# OLED-Clock-6-nl.net
KiCad netlist of a schematic drawn in EAGLE
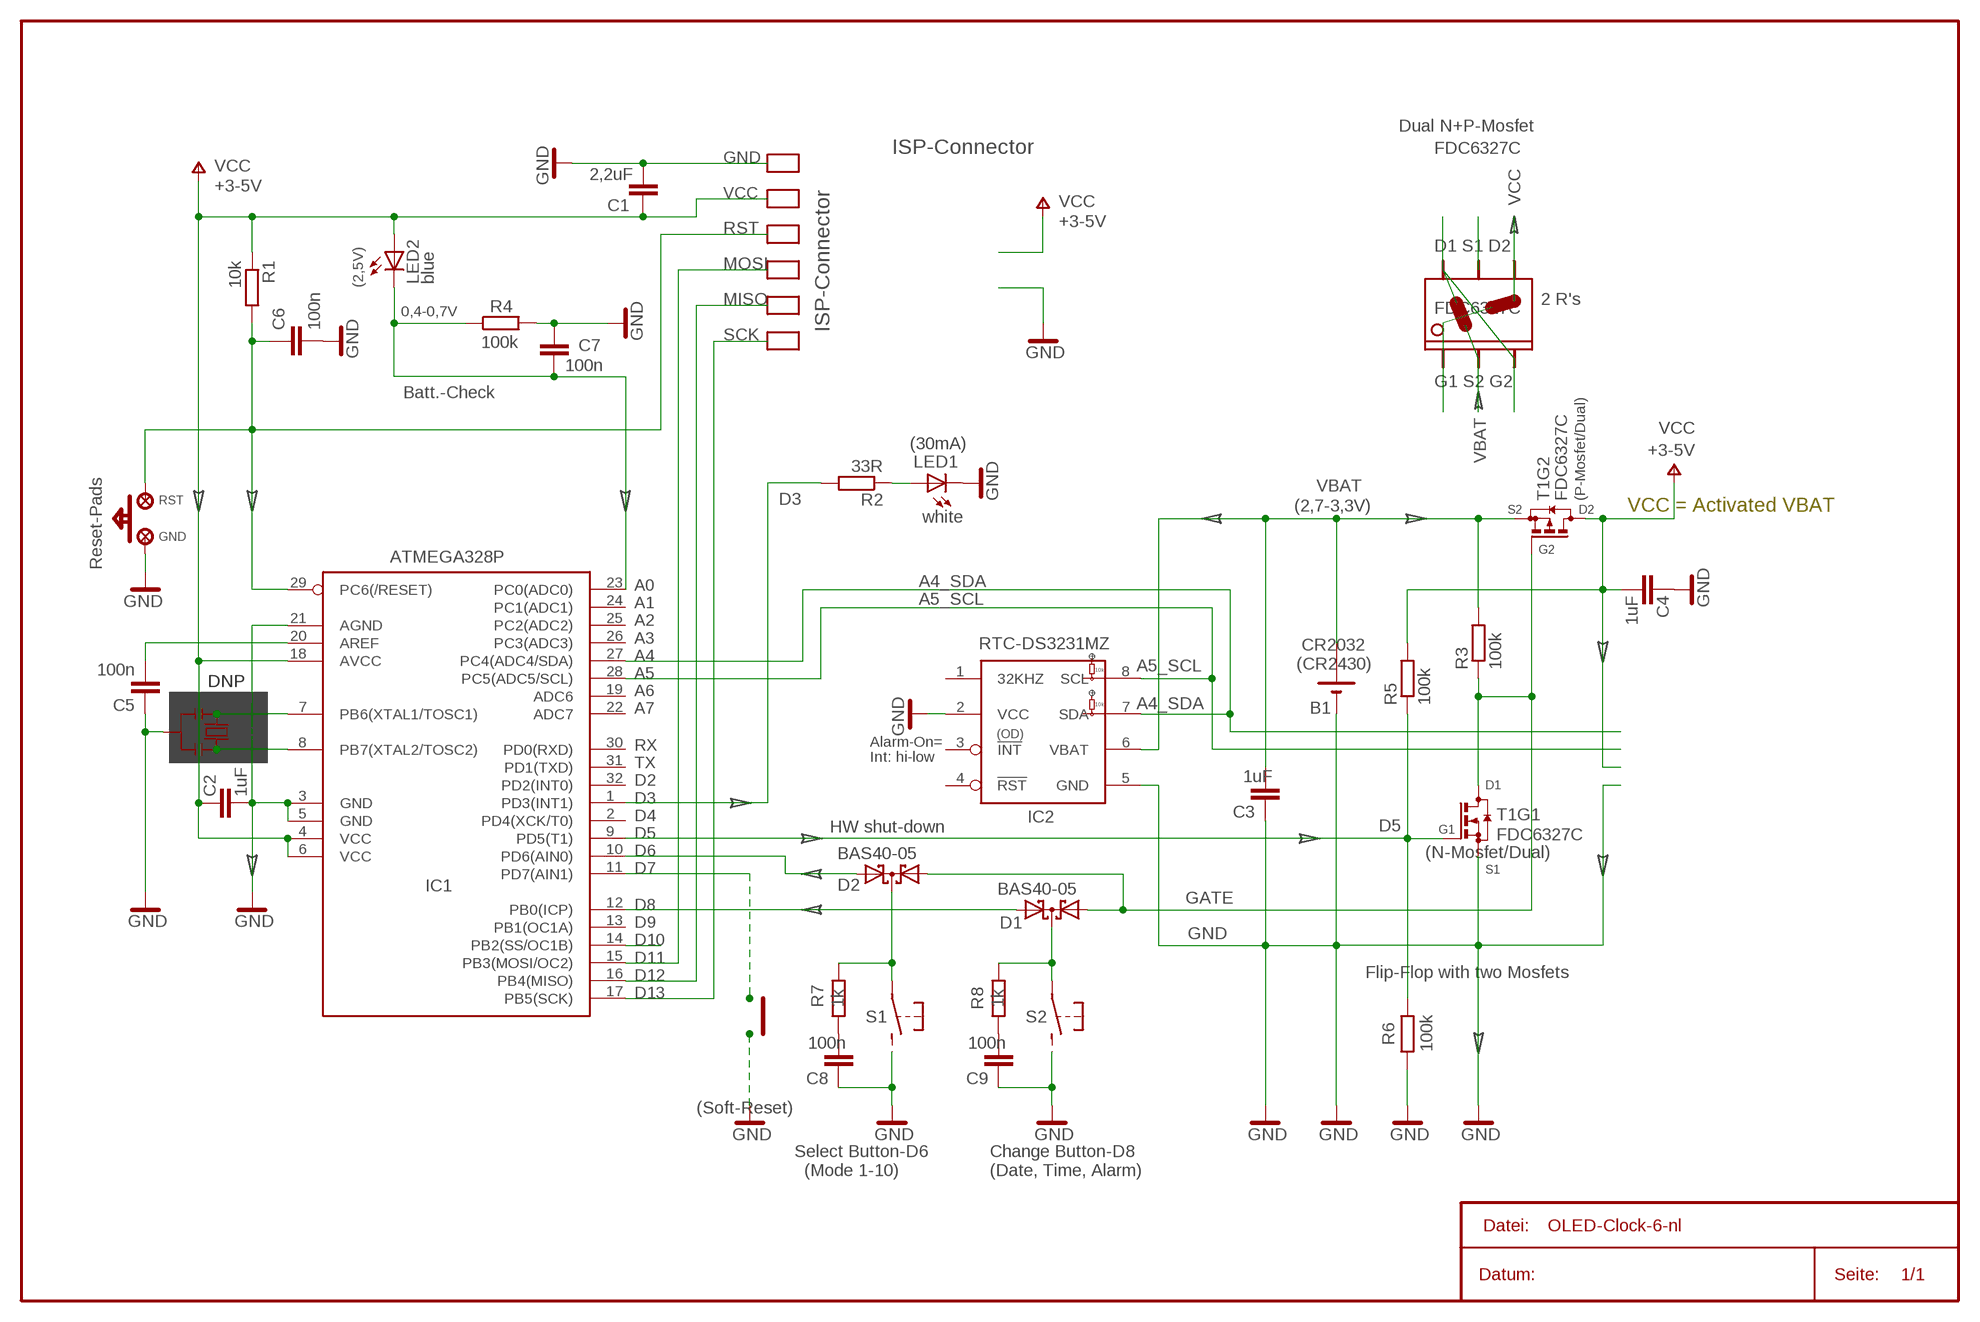
[diagram p0: schematic, sheet 1]

(export (version "E")
  (design (tool "Eeschema 10.0.6"))
  (components
    (comp (ref "C1")
      (value "2,2uF")
      (footprint "eagle-import:C0603")
      (libsource (lib "eagle-import") (part "C-EUC0603"))
    )
    (comp (ref "C2")
      (value "1uF")
      (footprint "eagle-import:C0603")
      (libsource (lib "eagle-import") (part "C-EUC0603"))
    )
    (comp (ref "C3")
      (value "1uF")
      (footprint "eagle-import:C0603")
      (libsource (lib "eagle-import") (part "C-EUC0603"))
    )
    (comp (ref "C4")
      (value "1uF")
      (footprint "eagle-import:C0603")
      (libsource (lib "eagle-import") (part "C-EUC0603"))
    )
    (comp (ref "C5")
      (value "100n")
      (footprint "eagle-import:C0603")
      (libsource (lib "eagle-import") (part "C-EUC0603"))
    )
    (comp (ref "C6")
      (value "100n")
      (footprint "eagle-import:C0603")
      (libsource (lib "eagle-import") (part "C-EUC0603"))
    )
    (comp (ref "C7")
      (value "100n")
      (footprint "eagle-import:C0603")
      (libsource (lib "eagle-import") (part "C-EUC0603"))
    )
    (comp (ref "C8")
      (value "100n")
      (footprint "eagle-import:C0603")
      (libsource (lib "eagle-import") (part "C-EUC0603"))
    )
    (comp (ref "C9")
      (value "100n")
      (footprint "eagle-import:C0603")
      (libsource (lib "eagle-import") (part "C-EUC0603"))
    )
    (comp (ref "D1")
      (value "BAS40-05")
      (footprint "eagle-import:SOT23")
      (libsource (lib "eagle-import") (part "BAS40-051"))
    )
    (comp (ref "D2")
      (value "BAS40-05")
      (footprint "eagle-import:SOT23")
      (libsource (lib "eagle-import") (part "BAS40-051"))
    )
    (comp (ref "GND")
      (value "LSP20")
      (footprint "eagle-import:LSP20")
      (libsource (lib "eagle-import") (part "LSP20"))
    )
    (comp (ref "IC1")
      (value "ATMEGA328P")
      (footprint "eagle-import:TQFP32-08")
      (libsource (lib "eagle-import") (part "MEGA8-AI"))
    )
    (comp (ref "IC2")
      (value "DS3231MZ")
      (footprint "eagle-import:SO08")
      (libsource (lib "eagle-import") (part "DS3231"))
    )
    (comp (ref "LED1")
      (value "white")
      (footprint "eagle-import:CHIPLED_1206")
      (libsource (lib "eagle-import") (part "LEDCHIPLED_1206"))
    )
    (comp (ref "LED2")
      (value "blue")
      (footprint "eagle-import:CHIPLED_0805")
      (libsource (lib "eagle-import") (part "LEDCHIPLED_0805"))
    )
    (comp (ref "R1")
      (value "10k")
      (footprint "eagle-import:R0603")
      (libsource (lib "eagle-import") (part "R-EU_R0603"))
    )
    (comp (ref "R2")
      (value "33R")
      (footprint "eagle-import:R0603")
      (libsource (lib "eagle-import") (part "R-EU_R0603"))
    )
    (comp (ref "R3")
      (value "100k")
      (footprint "eagle-import:R0603")
      (libsource (lib "eagle-import") (part "R-EU_R0603"))
    )
    (comp (ref "R4")
      (value "100k")
      (footprint "eagle-import:R0603")
      (libsource (lib "eagle-import") (part "R-EU_R0603"))
    )
    (comp (ref "R5")
      (value "100k")
      (footprint "eagle-import:R0603")
      (libsource (lib "eagle-import") (part "R-EU_R0603"))
    )
    (comp (ref "R6")
      (value "100k")
      (footprint "eagle-import:R0603")
      (libsource (lib "eagle-import") (part "R-EU_R0603"))
    )
    (comp (ref "R7")
      (value "1k")
      (footprint "eagle-import:R0603")
      (libsource (lib "eagle-import") (part "R-EU_R0603"))
    )
    (comp (ref "R8")
      (value "1k")
      (footprint "eagle-import:R0603")
      (libsource (lib "eagle-import") (part "R-EU_R0603"))
    )
    (comp (ref "RST")
      (value "LSP20")
      (footprint "eagle-import:LSP20")
      (libsource (lib "eagle-import") (part "LSP20"))
    )
    (comp (ref "T1")
      (value "FDC6327C")
      (footprint "eagle-import:SOT23-6")
      (libsource (lib "eagle-import") (part "NP_MOSFET_SOT23-6"))
    )
  )
  (nets
    (net (code "1") (name "/A4_SDA") (class "Default")
      (node (ref "IC1") (pin "27") (pinfunction "PC4(ADC4/SDA)_27") (pintype "bidirectional"))
      (node (ref "IC2") (pin "7") (pinfunction "SDA_7") (pintype "bidirectional"))
    )
    (net (code "2") (name "/A5_SCL") (class "Default")
      (node (ref "IC1") (pin "28") (pinfunction "PC5(ADC5/SCL)_28") (pintype "bidirectional"))
      (node (ref "IC2") (pin "8") (pinfunction "SCL_8") (pintype "bidirectional"))
    )
    (net (code "3") (name "/D3") (class "Default")
      (node (ref "IC1") (pin "1") (pinfunction "PD3(INT1)_1") (pintype "bidirectional"))
      (node (ref "R2") (pin "2") (pinfunction "2_2") (pintype "passive"))
    )
    (net (code "4") (name "/D5") (class "Default")
      (node (ref "IC1") (pin "9") (pinfunction "PD5(T1)_9") (pintype "bidirectional"))
      (node (ref "R5") (pin "1") (pinfunction "1_1") (pintype "passive"))
      (node (ref "R6") (pin "2") (pinfunction "2_2") (pintype "passive"))
      (node (ref "T1") (pin "1") (pinfunction "G_1") (pintype "passive"))
    )
    (net (code "5") (name "/GATE") (class "Default")
      (node (ref "D1") (pin "1") (pinfunction "A1_1") (pintype "passive"))
      (node (ref "D2") (pin "1") (pinfunction "A1_1") (pintype "passive"))
      (node (ref "R3") (pin "1") (pinfunction "1_1") (pintype "passive"))
      (node (ref "T1") (pin "3") (pinfunction "G_3") (pintype "passive"))
      (node (ref "T1") (pin "6") (pinfunction "D_6") (pintype "passive"))
    )
    (net (code "6") (name "/MISO") (class "Default")
      (node (ref "IC1") (pin "16") (pinfunction "PB4(MISO)_16") (pintype "bidirectional"))
    )
    (net (code "7") (name "/MOSI") (class "Default")
      (node (ref "IC1") (pin "15") (pinfunction "PB3(MOSI/OC2)_15") (pintype "bidirectional"))
    )
    (net (code "8") (name "/RST") (class "Default")
      (node (ref "C6") (pin "1") (pinfunction "1_1") (pintype "passive"))
      (node (ref "IC1") (pin "29") (pinfunction "PC6(/RESET)_29") (pintype "bidirectional"))
      (node (ref "R1") (pin "2") (pinfunction "2_2") (pintype "passive"))
      (node (ref "RST") (pin "P$1") (pinfunction "MP_P$1") (pintype "passive"))
    )
    (net (code "9") (name "/SCK") (class "Default")
      (node (ref "IC1") (pin "17") (pinfunction "PB5(SCK)_17") (pintype "bidirectional"))
    )
    (net (code "10") (name "/VBAT") (class "Default")
      (node (ref "C3") (pin "2") (pinfunction "2_2") (pintype "passive"))
      (node (ref "IC2") (pin "6") (pinfunction "VBAT_6") (pintype "bidirectional"))
      (node (ref "R3") (pin "2") (pinfunction "2_2") (pintype "passive"))
      (node (ref "T1") (pin "2") (pinfunction "S_2") (pintype "passive"))
    )
    (net (code "11") (name "GND") (class "Default")
      (node (ref "C1") (pin "2") (pinfunction "2_2") (pintype "passive"))
      (node (ref "C2") (pin "2") (pinfunction "2_2") (pintype "passive"))
      (node (ref "C3") (pin "1") (pinfunction "1_1") (pintype "passive"))
      (node (ref "C4") (pin "1") (pinfunction "1_1") (pintype "passive"))
      (node (ref "C5") (pin "1") (pinfunction "1_1") (pintype "passive"))
      (node (ref "C6") (pin "2") (pinfunction "2_2") (pintype "passive"))
      (node (ref "C7") (pin "2") (pinfunction "2_2") (pintype "passive"))
      (node (ref "C8") (pin "1") (pinfunction "1_1") (pintype "passive"))
      (node (ref "C9") (pin "1") (pinfunction "1_1") (pintype "passive"))
      (node (ref "GND") (pin "P$1") (pinfunction "MP_P$1") (pintype "passive"))
      (node (ref "IC1") (pin "21") (pinfunction "AGND_21") (pintype "bidirectional"))
      (node (ref "IC1") (pin "3") (pinfunction "GND_3") (pintype "bidirectional"))
      (node (ref "IC1") (pin "5") (pinfunction "GND_5") (pintype "bidirectional"))
      (node (ref "IC2") (pin "2") (pinfunction "VCC_2") (pintype "input"))
      (node (ref "IC2") (pin "5") (pinfunction "GND_5") (pintype "bidirectional"))
      (node (ref "LED1") (pin "C") (pinfunction "C_C") (pintype "passive"))
      (node (ref "R4") (pin "2") (pinfunction "2_2") (pintype "passive"))
      (node (ref "R6") (pin "1") (pinfunction "1_1") (pintype "passive"))
      (node (ref "T1") (pin "5") (pinfunction "S_5") (pintype "passive"))
    )
    (net (code "12") (name "Net-(C8-Pad2)") (class "Default")
      (node (ref "C8") (pin "2") (pinfunction "2_2") (pintype "passive"))
      (node (ref "R7") (pin "1") (pinfunction "1_1") (pintype "passive"))
    )
    (net (code "13") (name "Net-(C9-Pad2)") (class "Default")
      (node (ref "C9") (pin "2") (pinfunction "2_2") (pintype "passive"))
      (node (ref "R8") (pin "1") (pinfunction "1_1") (pintype "passive"))
    )
    (net (code "14") (name "Net-(D1-A2)") (class "Default")
      (node (ref "D1") (pin "2") (pinfunction "A2_2") (pintype "passive"))
      (node (ref "IC1") (pin "12") (pinfunction "PB0(ICP)_12") (pintype "bidirectional"))
    )
    (net (code "15") (name "Net-(D1-C)") (class "Default")
      (node (ref "D1") (pin "3") (pinfunction "C_3") (pintype "passive"))
      (node (ref "R8") (pin "2") (pinfunction "2_2") (pintype "passive"))
    )
    (net (code "16") (name "Net-(D2-A2)") (class "Default")
      (node (ref "D2") (pin "2") (pinfunction "A2_2") (pintype "passive"))
      (node (ref "IC1") (pin "10") (pinfunction "PD6(AIN0)_10") (pintype "bidirectional"))
    )
    (net (code "17") (name "Net-(D2-C)") (class "Default")
      (node (ref "D2") (pin "3") (pinfunction "C_3") (pintype "passive"))
      (node (ref "R7") (pin "2") (pinfunction "2_2") (pintype "passive"))
    )
    (net (code "18") (name "Net-(IC1-AREF)") (class "Default")
      (node (ref "C5") (pin "2") (pinfunction "2_2") (pintype "passive"))
      (node (ref "IC1") (pin "20") (pinfunction "AREF_20") (pintype "bidirectional"))
    )
    (net (code "19") (name "Net-(IC1-PC0(ADC0))") (class "Default")
      (node (ref "C7") (pin "1") (pinfunction "1_1") (pintype "passive"))
      (node (ref "IC1") (pin "23") (pinfunction "PC0(ADC0)_23") (pintype "bidirectional"))
      (node (ref "LED2") (pin "C") (pinfunction "C_C") (pintype "passive"))
      (node (ref "R4") (pin "1") (pinfunction "1_1") (pintype "passive"))
    )
    (net (code "20") (name "Net-(LED1-PadA)") (class "Default")
      (node (ref "LED1") (pin "A") (pinfunction "A_A") (pintype "passive"))
      (node (ref "R2") (pin "1") (pinfunction "1_1") (pintype "passive"))
    )
    (net (code "21") (name "VCC") (class "Default")
      (node (ref "C1") (pin "1") (pinfunction "1_1") (pintype "passive"))
      (node (ref "C2") (pin "1") (pinfunction "1_1") (pintype "passive"))
      (node (ref "C4") (pin "2") (pinfunction "2_2") (pintype "passive"))
      (node (ref "IC1") (pin "18") (pinfunction "AVCC_18") (pintype "bidirectional"))
      (node (ref "IC1") (pin "4") (pinfunction "VCC_4") (pintype "bidirectional"))
      (node (ref "IC1") (pin "6") (pinfunction "VCC_6") (pintype "bidirectional"))
      (node (ref "LED2") (pin "A") (pinfunction "A_A") (pintype "passive"))
      (node (ref "R1") (pin "1") (pinfunction "1_1") (pintype "passive"))
      (node (ref "R5") (pin "2") (pinfunction "2_2") (pintype "passive"))
      (node (ref "T1") (pin "4") (pinfunction "D_4") (pintype "passive"))
    )
    (net (code "22") (name "unconnected-(IC1-ADC6-Pad19)") (class "Default")
      (node (ref "IC1") (pin "19") (pinfunction "ADC6_19") (pintype "bidirectional"))
    )
    (net (code "23") (name "unconnected-(IC1-ADC7-Pad22)") (class "Default")
      (node (ref "IC1") (pin "22") (pinfunction "ADC7_22") (pintype "bidirectional"))
    )
    (net (code "24") (name "unconnected-(IC1-PB1(OC1A)-Pad13)") (class "Default")
      (node (ref "IC1") (pin "13") (pinfunction "PB1(OC1A)_13") (pintype "bidirectional"))
    )
    (net (code "25") (name "unconnected-(IC1-PB2(SS{slash}OC1B)-Pad14)") (class "Default")
      (node (ref "IC1") (pin "14") (pinfunction "PB2(SS/OC1B)_14") (pintype "bidirectional"))
    )
    (net (code "26") (name "unconnected-(IC1-PB6(XTAL1{slash}TOSC1)-Pad7)") (class "Default")
      (node (ref "IC1") (pin "7") (pinfunction "PB6(XTAL1/TOSC1)_7") (pintype "bidirectional"))
    )
    (net (code "27") (name "unconnected-(IC1-PB7(XTAL2{slash}TOSC2)-Pad8)") (class "Default")
      (node (ref "IC1") (pin "8") (pinfunction "PB7(XTAL2/TOSC2)_8") (pintype "bidirectional"))
    )
    (net (code "28") (name "unconnected-(IC1-PC1(ADC1)-Pad24)") (class "Default")
      (node (ref "IC1") (pin "24") (pinfunction "PC1(ADC1)_24") (pintype "bidirectional"))
    )
    (net (code "29") (name "unconnected-(IC1-PC2(ADC2)-Pad25)") (class "Default")
      (node (ref "IC1") (pin "25") (pinfunction "PC2(ADC2)_25") (pintype "bidirectional"))
    )
    (net (code "30") (name "unconnected-(IC1-PC3(ADC3)-Pad26)") (class "Default")
      (node (ref "IC1") (pin "26") (pinfunction "PC3(ADC3)_26") (pintype "bidirectional"))
    )
    (net (code "31") (name "unconnected-(IC1-PD0(RXD)-Pad30)") (class "Default")
      (node (ref "IC1") (pin "30") (pinfunction "PD0(RXD)_30") (pintype "bidirectional"))
    )
    (net (code "32") (name "unconnected-(IC1-PD1(TXD)-Pad31)") (class "Default")
      (node (ref "IC1") (pin "31") (pinfunction "PD1(TXD)_31") (pintype "bidirectional"))
    )
    (net (code "33") (name "unconnected-(IC1-PD2(INT0)-Pad32)") (class "Default")
      (node (ref "IC1") (pin "32") (pinfunction "PD2(INT0)_32") (pintype "bidirectional"))
    )
    (net (code "34") (name "unconnected-(IC1-PD4(XCK{slash}T0)-Pad2)") (class "Default")
      (node (ref "IC1") (pin "2") (pinfunction "PD4(XCK/T0)_2") (pintype "bidirectional"))
    )
    (net (code "35") (name "unconnected-(IC1-PD7(AIN1)-Pad11)") (class "Default")
      (node (ref "IC1") (pin "11") (pinfunction "PD7(AIN1)_11") (pintype "bidirectional"))
    )
    (net (code "36") (name "unconnected-(IC2-32KHZ-Pad1)") (class "Default")
      (node (ref "IC2") (pin "1") (pinfunction "32KHZ_1") (pintype "output"))
    )
    (net (code "37") (name "unconnected-(IC2-~{INT}-Pad3)") (class "Default")
      (node (ref "IC2") (pin "3") (pinfunction "~{INT}_3") (pintype "bidirectional"))
    )
    (net (code "38") (name "unconnected-(IC2-~{RST}-Pad4)") (class "Default")
      (node (ref "IC2") (pin "4") (pinfunction "~{RST}_4") (pintype "bidirectional"))
    )
  )
)
